# RTC-Module.net
KiCad netlist of a schematic drawn in EAGLE
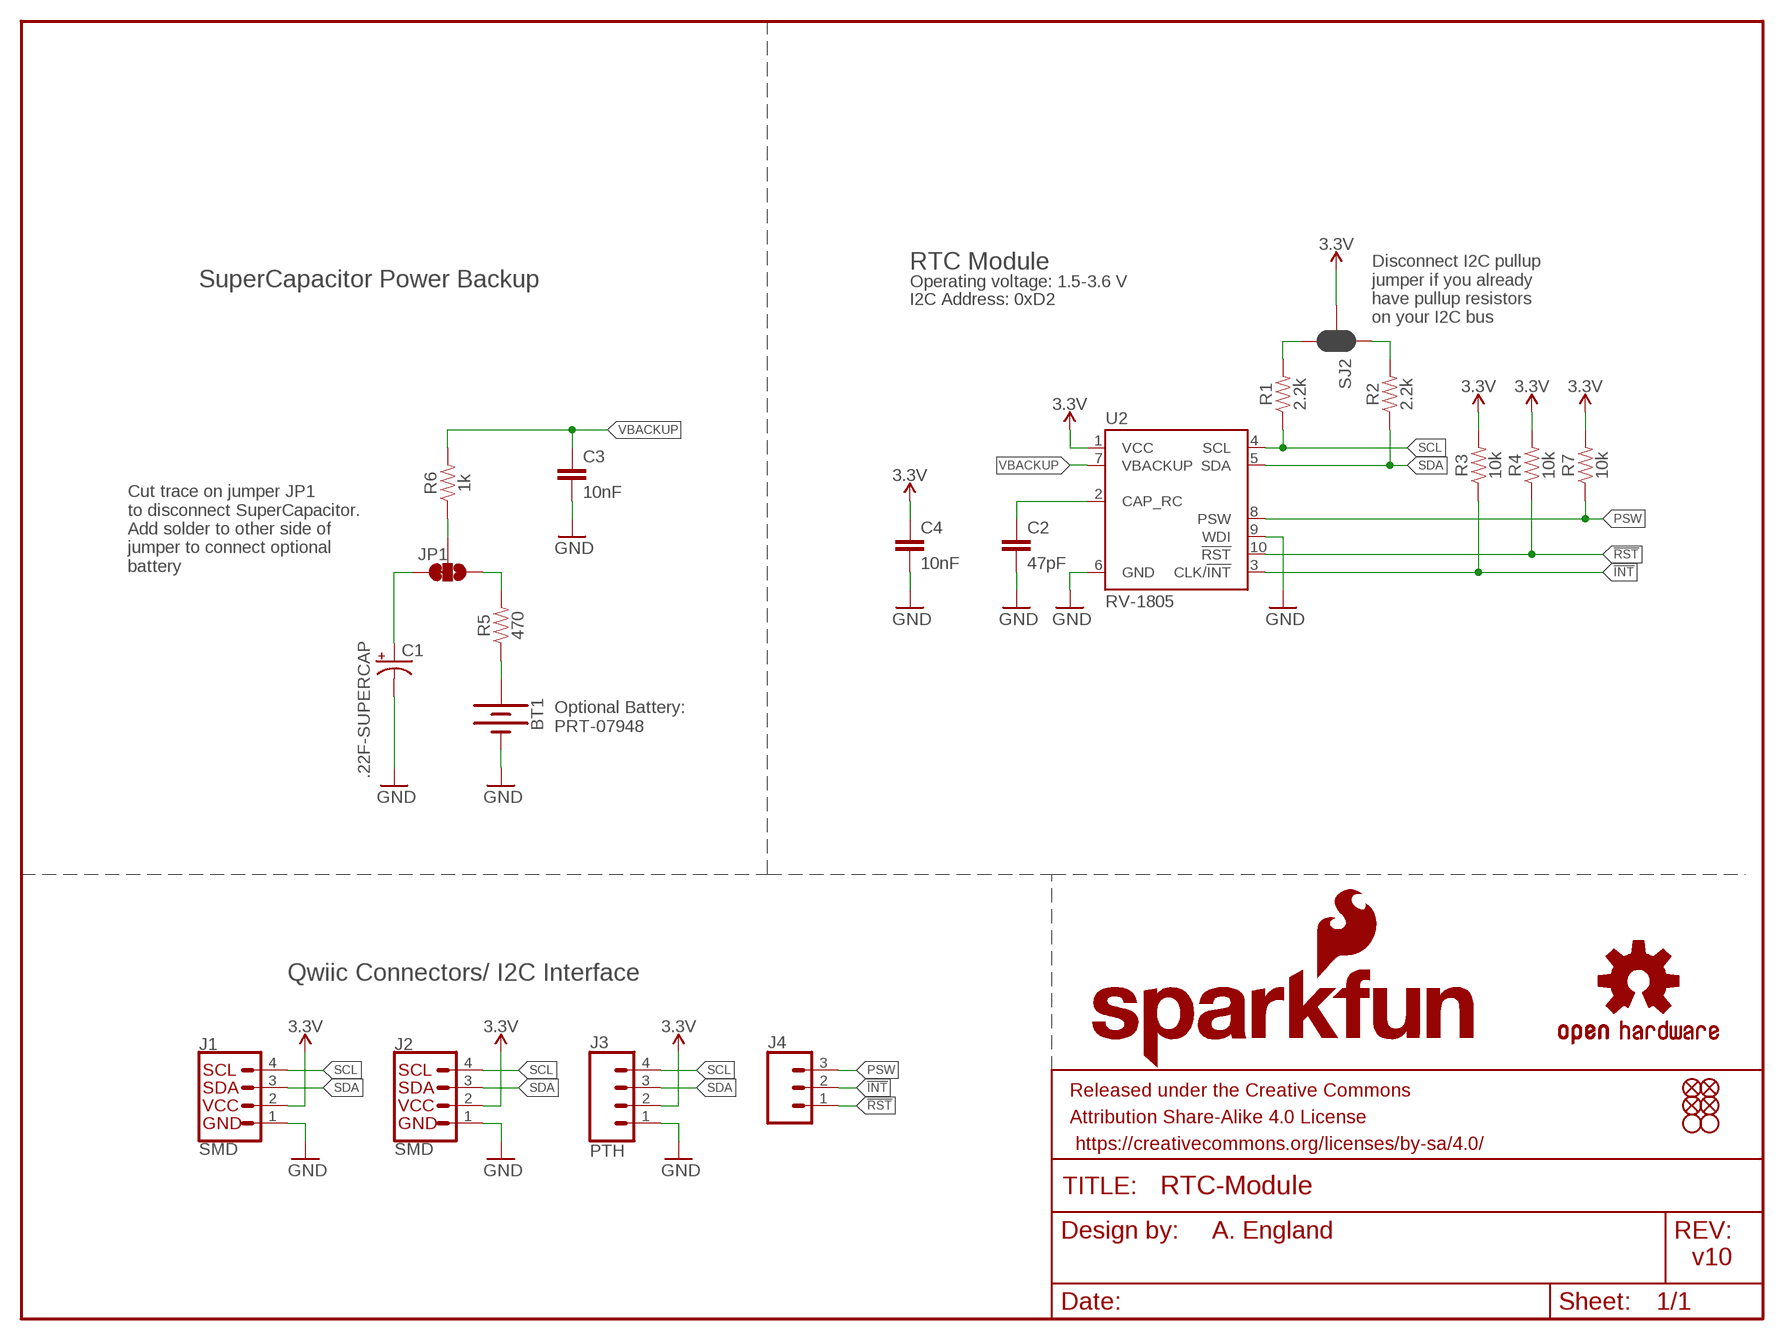
[diagram p0: schematic, sheet 1]

(export (version "E")
  (design (tool "Eeschema 10.0.6"))
  (components
    (comp (ref "BT1")
      (value "BATTERY-12MM_PTH")
      (footprint "eagle-import:BATTCON_12MM_PTH")
      (libsource (lib "eagle-import") (part "BATTERY-12MM_PTH"))
    )
    (comp (ref "C1")
      (value ".22F-SUPERCAP")
      (footprint "eagle-import:DSK-RADIAL-6.8MM")
      (libsource (lib "eagle-import") (part ".22F-SUPERCAP"))
    )
    (comp (ref "C2")
      (value "47pF")
      (footprint "eagle-import:0603")
      (libsource (lib "eagle-import") (part "47PF-0603-50V-5%"))
    )
    (comp (ref "C3")
      (value "10nF")
      (footprint "eagle-import:0603")
      (libsource (lib "eagle-import") (part "10NF-0603-50V-10%"))
    )
    (comp (ref "C4")
      (value "10nF")
      (footprint "eagle-import:0603")
      (libsource (lib "eagle-import") (part "10NF-0603-50V-10%"))
    )
    (comp (ref "FD1")
      (value "FIDUCIALUFIDUCIAL")
      (footprint "eagle-import:FIDUCIAL-MICRO")
      (libsource (lib "eagle-import") (part "FIDUCIALUFIDUCIAL"))
    )
    (comp (ref "FD2")
      (value "FIDUCIALUFIDUCIAL")
      (footprint "eagle-import:FIDUCIAL-MICRO")
      (libsource (lib "eagle-import") (part "FIDUCIALUFIDUCIAL"))
    )
    (comp (ref "FD3")
      (value "FIDUCIALUFIDUCIAL")
      (footprint "eagle-import:FIDUCIAL-MICRO")
      (libsource (lib "eagle-import") (part "FIDUCIALUFIDUCIAL"))
    )
    (comp (ref "FD4")
      (value "FIDUCIALUFIDUCIAL")
      (footprint "eagle-import:FIDUCIAL-MICRO")
      (libsource (lib "eagle-import") (part "FIDUCIALUFIDUCIAL"))
    )
    (comp (ref "FRAME2")
      (value "FRAME-LETTER")
      (footprint "eagle-import:CREATIVE_COMMONS")
      (libsource (lib "eagle-import") (part "FRAME-LETTER"))
    )
    (comp (ref "J1")
      (value "SMD")
      (footprint "eagle-import:1X04_1MM_RA")
      (libsource (lib "eagle-import") (part "QWIIC_CONNECTORJS-1MM"))
    )
    (comp (ref "J2")
      (value "SMD")
      (footprint "eagle-import:1X04_1MM_RA")
      (libsource (lib "eagle-import") (part "QWIIC_CONNECTORJS-1MM"))
    )
    (comp (ref "J3")
      (value "PTH")
      (footprint "eagle-import:1X04_NO_SILK")
      (libsource (lib "eagle-import") (part "CONN_041X04_NO_SILK"))
    )
    (comp (ref "J4")
      (value "CONN_031X03_NO_SILK")
      (footprint "eagle-import:1X03_NO_SILK")
      (libsource (lib "eagle-import") (part "CONN_031X03_NO_SILK"))
    )
    (comp (ref "JP1")
      (value "JUMPER-SMT_3_1-NC_TRACE_NO-SILK")
      (footprint "eagle-import:SMT-JUMPER_3_1-NC_TRACE_NO-SILK")
      (libsource (lib "eagle-import") (part "JUMPER-SMT_3_1-NC_TRACE_NO-SILK"))
    )
    (comp (ref "LOGO1")
      (value "OSHW-LOGOS")
      (footprint "eagle-import:OSHW-LOGO-S")
      (libsource (lib "eagle-import") (part "OSHW-LOGOS"))
    )
    (comp (ref "LOGO2")
      (value "SFE_LOGO_NAME_FLAME.1_INCH")
      (footprint "eagle-import:SFE_LOGO_NAME_FLAME_.1")
      (libsource (lib "eagle-import") (part "SFE_LOGO_NAME_FLAME.1_INCH"))
    )
    (comp (ref "LOGO3")
      (value "SFE_LOGO_NAME_FLAME.1_INCH")
      (footprint "eagle-import:SFE_LOGO_NAME_FLAME_.1")
      (libsource (lib "eagle-import") (part "SFE_LOGO_NAME_FLAME.1_INCH"))
    )
    (comp (ref "R1")
      (value "2.2k")
      (footprint "eagle-import:0603")
      (libsource (lib "eagle-import") (part "2.2KOHM-0603-1/10W-1%"))
    )
    (comp (ref "R2")
      (value "2.2k")
      (footprint "eagle-import:0603")
      (libsource (lib "eagle-import") (part "2.2KOHM-0603-1/10W-1%"))
    )
    (comp (ref "R3")
      (value "10k")
      (footprint "eagle-import:0603")
      (libsource (lib "eagle-import") (part "10KOHM-0603-1/10W-1%"))
    )
    (comp (ref "R4")
      (value "10k")
      (footprint "eagle-import:0603")
      (libsource (lib "eagle-import") (part "10KOHM-0603-1/10W-1%"))
    )
    (comp (ref "R5")
      (value "470")
      (footprint "eagle-import:0603")
      (libsource (lib "eagle-import") (part "470OHM-0603-1/10W-1%"))
    )
    (comp (ref "R6")
      (value "1k")
      (footprint "eagle-import:0603")
      (libsource (lib "eagle-import") (part "1KOHM-0603-1/10W-1%"))
    )
    (comp (ref "R7")
      (value "10k")
      (footprint "eagle-import:0603")
      (libsource (lib "eagle-import") (part "10KOHM-0603-1/10W-1%"))
    )
    (comp (ref "SJ2")
      (value "JUMPER-SMT_3_2-NC_PASTE_SILK")
      (footprint "eagle-import:SMT-JUMPER_3_2-NC_PASTE_SILK")
      (libsource (lib "eagle-import") (part "JUMPER-SMT_3_2-NC_PASTE_SILK"))
    )
    (comp (ref "U$6")
      (value "STAND-OFF")
      (footprint "eagle-import:STAND-OFF")
      (libsource (lib "eagle-import") (part "STAND-OFF"))
    )
    (comp (ref "U$7")
      (value "STAND-OFF")
      (footprint "eagle-import:STAND-OFF")
      (libsource (lib "eagle-import") (part "STAND-OFF"))
    )
    (comp (ref "U2")
      (value "RV-1805")
      (footprint "eagle-import:RV-1805")
      (libsource (lib "eagle-import") (part "RV-1805"))
    )
  )
  (nets
    (net (code "1") (name "/~{INT}") (class "Default")
      (node (ref "J4") (pin "2") (pinfunction "2_2") (pintype "passive"))
      (node (ref "R3") (pin "1") (pinfunction "1_1") (pintype "passive"))
      (node (ref "U2") (pin "3") (pinfunction "CLK/~{INT}_3") (pintype "bidirectional"))
    )
    (net (code "2") (name "/~{RST}") (class "Default")
      (node (ref "J4") (pin "1") (pinfunction "1_1") (pintype "passive"))
      (node (ref "R4") (pin "1") (pinfunction "1_1") (pintype "passive"))
      (node (ref "U2") (pin "10") (pinfunction "~{RST}_10") (pintype "bidirectional"))
    )
    (net (code "3") (name "3.3V") (class "Default")
      (node (ref "C4") (pin "1") (pinfunction "1_1") (pintype "passive"))
      (node (ref "J1") (pin "2") (pinfunction "2_2") (pintype "power_in"))
      (node (ref "J2") (pin "2") (pinfunction "2_2") (pintype "power_in"))
      (node (ref "J3") (pin "2") (pinfunction "2_2") (pintype "passive"))
      (node (ref "R3") (pin "2") (pinfunction "2_2") (pintype "passive"))
      (node (ref "R4") (pin "2") (pinfunction "2_2") (pintype "passive"))
      (node (ref "R7") (pin "2") (pinfunction "2_2") (pintype "passive"))
      (node (ref "SJ2") (pin "2") (pinfunction "2_2") (pintype "passive"))
      (node (ref "U2") (pin "1") (pinfunction "VCC_1") (pintype "bidirectional"))
    )
    (net (code "4") (name "GND") (class "Default")
      (node (ref "BT1") (pin "GND") (pinfunction "-_GND") (pintype "power_in"))
      (node (ref "C1") (pin "-") (pinfunction "-_-") (pintype "passive"))
      (node (ref "C2") (pin "2") (pinfunction "2_2") (pintype "passive"))
      (node (ref "C3") (pin "2") (pinfunction "2_2") (pintype "passive"))
      (node (ref "C4") (pin "2") (pinfunction "2_2") (pintype "passive"))
      (node (ref "J1") (pin "1") (pinfunction "1_1") (pintype "power_in"))
      (node (ref "J2") (pin "1") (pinfunction "1_1") (pintype "power_in"))
      (node (ref "J3") (pin "1") (pinfunction "1_1") (pintype "passive"))
      (node (ref "U2") (pin "6") (pinfunction "GND_6") (pintype "bidirectional"))
      (node (ref "U2") (pin "9") (pinfunction "WDI_9") (pintype "bidirectional"))
    )
    (net (code "5") (name "Net-(BT1-+)") (class "Default")
      (node (ref "BT1") (pin "VCC@1") (pinfunction "+_VCC@1") (pintype "power_in"))
      (node (ref "R5") (pin "1") (pinfunction "1_1") (pintype "passive"))
    )
    (net (code "6") (name "Net-(C1-Pad+)") (class "Default")
      (node (ref "C1") (pin "+") (pinfunction "+_+") (pintype "passive"))
      (node (ref "JP1") (pin "3") (pinfunction "3_3") (pintype "passive"))
    )
    (net (code "7") (name "Net-(JP1-Pad1)") (class "Default")
      (node (ref "JP1") (pin "1") (pinfunction "1_1") (pintype "passive"))
      (node (ref "R5") (pin "2") (pinfunction "2_2") (pintype "passive"))
    )
    (net (code "8") (name "Net-(JP1-Pad2)") (class "Default")
      (node (ref "JP1") (pin "2") (pinfunction "2_2") (pintype "passive"))
      (node (ref "R6") (pin "1") (pinfunction "1_1") (pintype "passive"))
    )
    (net (code "9") (name "Net-(R1-Pad2)") (class "Default")
      (node (ref "R1") (pin "2") (pinfunction "2_2") (pintype "passive"))
      (node (ref "SJ2") (pin "3") (pinfunction "3_3") (pintype "passive"))
    )
    (net (code "10") (name "Net-(R2-Pad2)") (class "Default")
      (node (ref "R2") (pin "2") (pinfunction "2_2") (pintype "passive"))
      (node (ref "SJ2") (pin "1") (pinfunction "1_1") (pintype "passive"))
    )
    (net (code "11") (name "Net-(U2-CAP_RC)") (class "Default")
      (node (ref "C2") (pin "1") (pinfunction "1_1") (pintype "passive"))
      (node (ref "U2") (pin "2") (pinfunction "CAP_RC_2") (pintype "bidirectional"))
    )
    (net (code "12") (name "PSW") (class "Default")
      (node (ref "J4") (pin "3") (pinfunction "3_3") (pintype "passive"))
      (node (ref "R7") (pin "1") (pinfunction "1_1") (pintype "passive"))
      (node (ref "U2") (pin "8") (pinfunction "PSW_8") (pintype "bidirectional"))
    )
    (net (code "13") (name "SCL") (class "Default")
      (node (ref "J1") (pin "4") (pinfunction "4_4") (pintype "passive"))
      (node (ref "J2") (pin "4") (pinfunction "4_4") (pintype "passive"))
      (node (ref "J3") (pin "4") (pinfunction "4_4") (pintype "passive"))
      (node (ref "R1") (pin "1") (pinfunction "1_1") (pintype "passive"))
      (node (ref "U2") (pin "4") (pinfunction "SCL_4") (pintype "bidirectional"))
    )
    (net (code "14") (name "SDA") (class "Default")
      (node (ref "J1") (pin "3") (pinfunction "3_3") (pintype "passive"))
      (node (ref "J2") (pin "3") (pinfunction "3_3") (pintype "passive"))
      (node (ref "J3") (pin "3") (pinfunction "3_3") (pintype "passive"))
      (node (ref "R2") (pin "1") (pinfunction "1_1") (pintype "passive"))
      (node (ref "U2") (pin "5") (pinfunction "SDA_5") (pintype "bidirectional"))
    )
    (net (code "15") (name "VBACKUP") (class "Default")
      (node (ref "C3") (pin "1") (pinfunction "1_1") (pintype "passive"))
      (node (ref "R6") (pin "2") (pinfunction "2_2") (pintype "passive"))
      (node (ref "U2") (pin "7") (pinfunction "VBACKUP_7") (pintype "bidirectional"))
    )
  )
)
